# CNCdriver.net
KiCad netlist of a schematic drawn in EAGLE
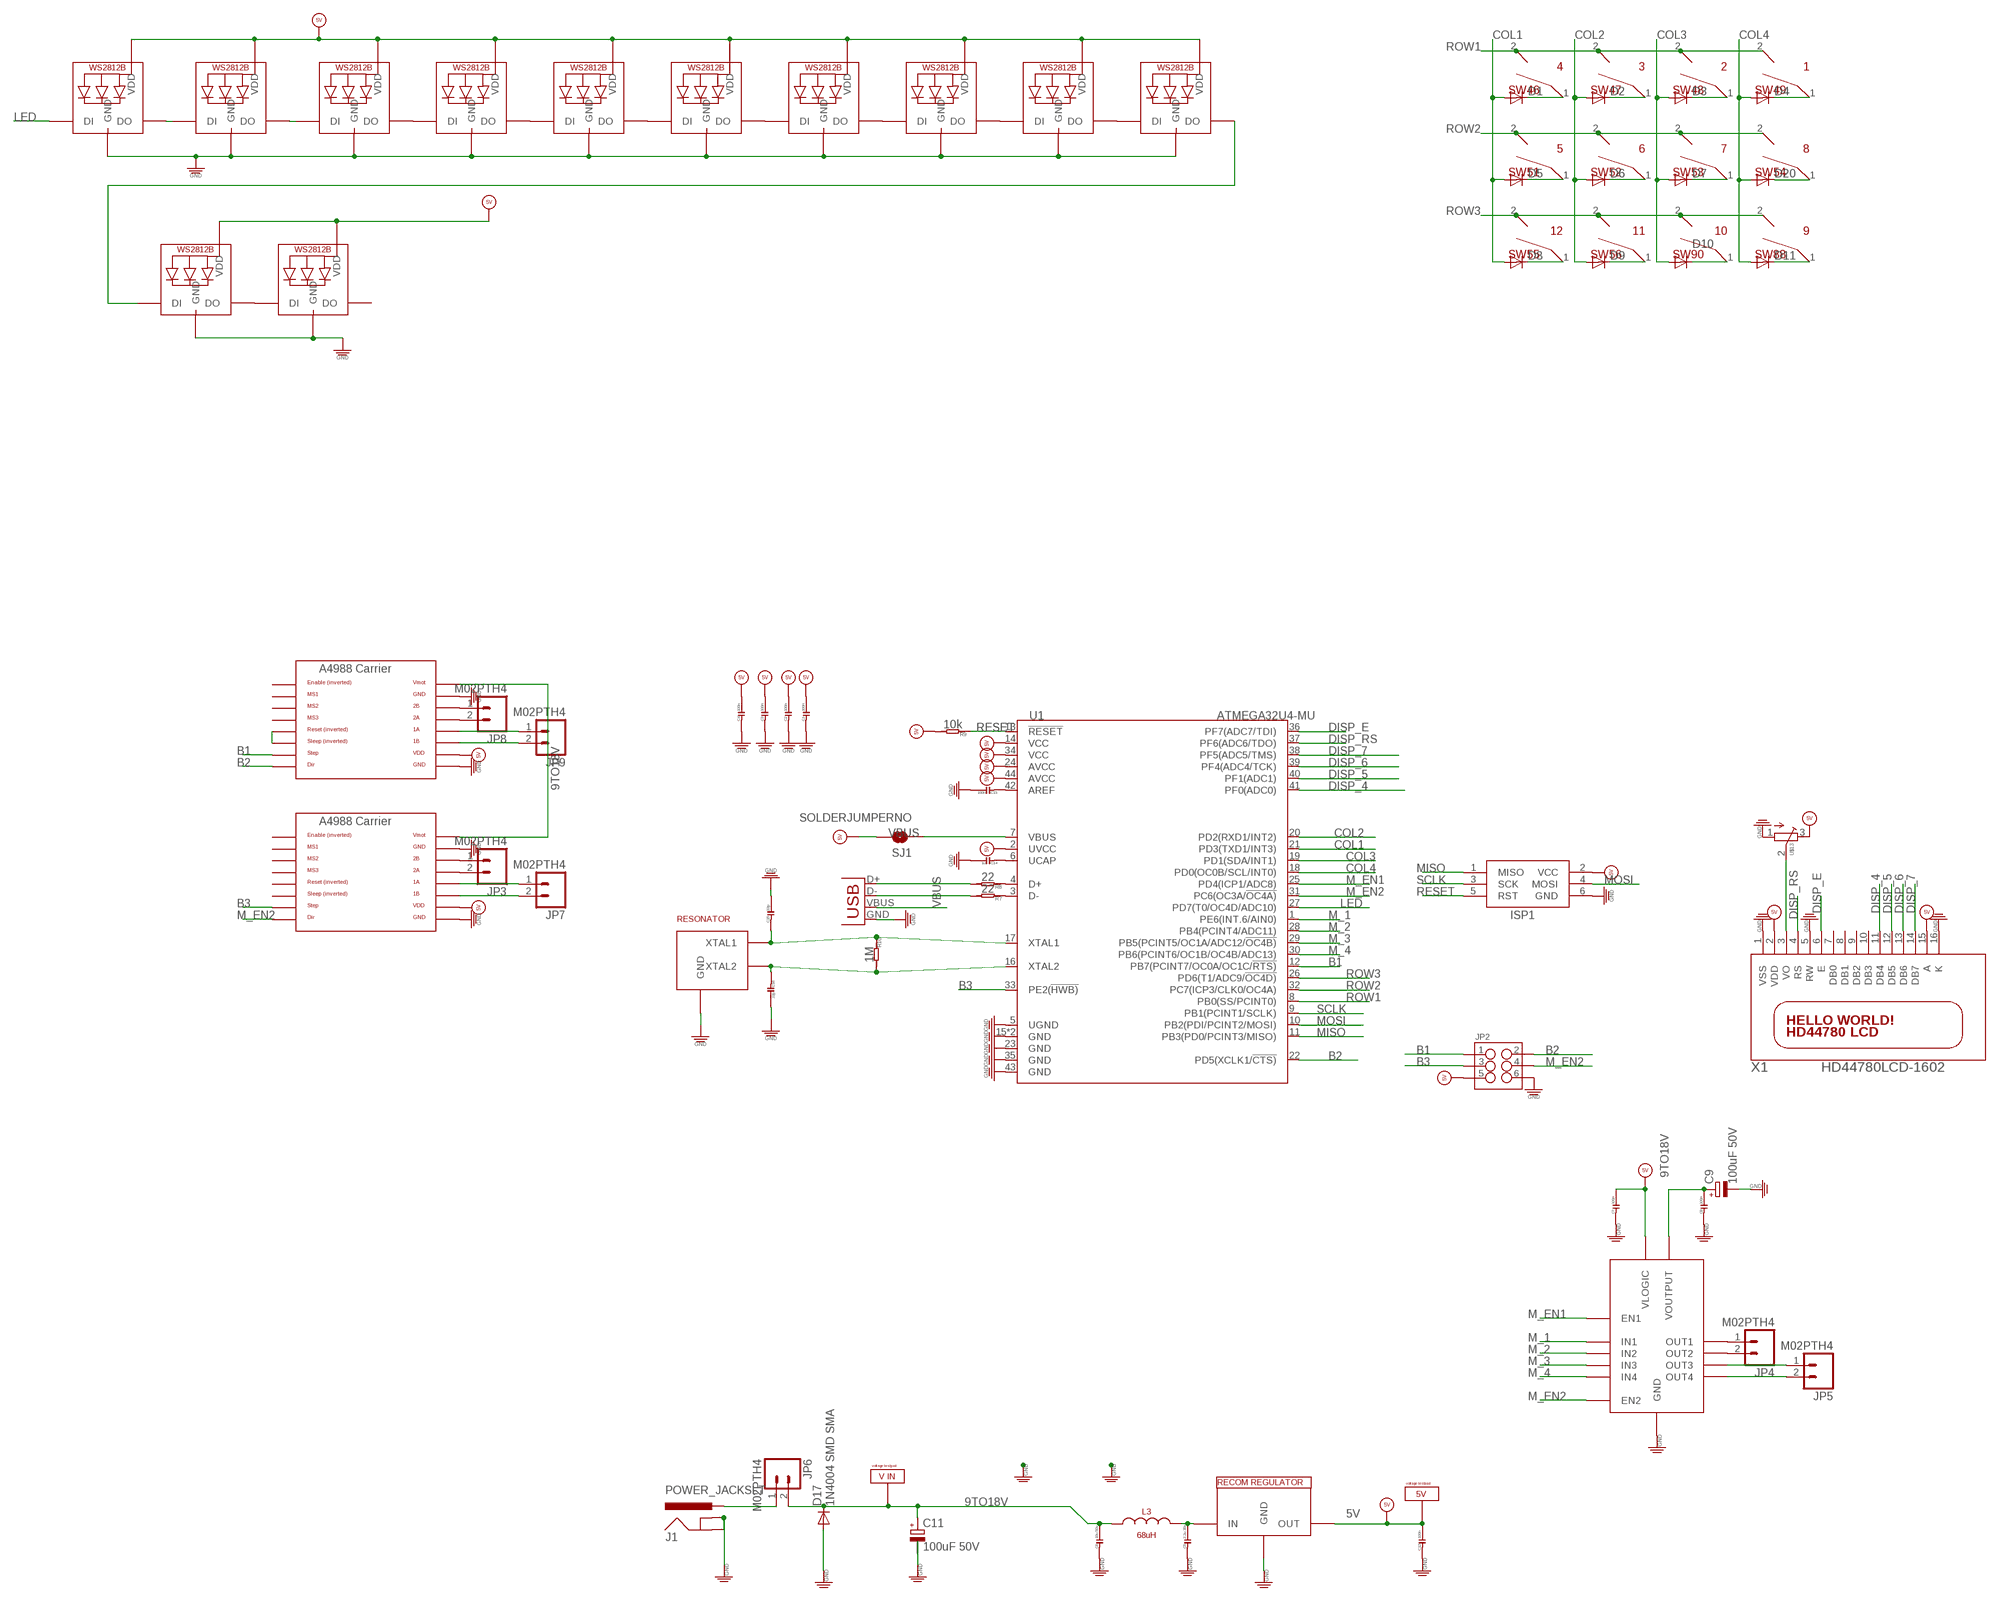
[diagram p0: schematic, sheet 1]

(export (version "E")
  (design (tool "Eeschema 10.0.6"))
  (components
    (comp (ref "C1")
      (value "100n")
      (footprint "eagle-import:C0603")
      (libsource (lib "eagle-import") (part "C-0603"))
    )
    (comp (ref "C2")
      (value "100n")
      (footprint "eagle-import:C0603")
      (libsource (lib "eagle-import") (part "C-0603"))
    )
    (comp (ref "C3")
      (value "100n")
      (footprint "eagle-import:C0603")
      (libsource (lib "eagle-import") (part "C-0603"))
    )
    (comp (ref "C4")
      (value "100n")
      (footprint "eagle-import:C0603")
      (libsource (lib "eagle-import") (part "C-0603"))
    )
    (comp (ref "C5")
      (value "2.2u 35v")
      (footprint "eagle-import:C0603")
      (libsource (lib "eagle-import") (part "C-0603"))
    )
    (comp (ref "C6")
      (value "10u 50v")
      (footprint "eagle-import:C0603")
      (libsource (lib "eagle-import") (part "C-0603"))
    )
    (comp (ref "C7")
      (value "100n")
      (footprint "eagle-import:C0603")
      (libsource (lib "eagle-import") (part "C-0603"))
    )
    (comp (ref "C8")
      (value "100n")
      (footprint "eagle-import:C0603")
      (libsource (lib "eagle-import") (part "C-0603"))
    )
    (comp (ref "C9")
      (value "100uF 50V")
      (footprint "eagle-import:153CLV-1010")
      (libsource (lib "eagle-import") (part "CPOL-EU153CLV-1010"))
    )
    (comp (ref "C11")
      (value "100uF 50V")
      (footprint "eagle-import:153CLV-1010")
      (libsource (lib "eagle-import") (part "CPOL-EU153CLV-1010"))
    )
    (comp (ref "C12")
      (value "100n")
      (footprint "eagle-import:C0603")
      (libsource (lib "eagle-import") (part "C-0603"))
    )
    (comp (ref "C13")
      (value "100n")
      (footprint "eagle-import:C0603")
      (libsource (lib "eagle-import") (part "C-0603"))
    )
    (comp (ref "C14")
      (value "1u")
      (footprint "eagle-import:C0603")
      (libsource (lib "eagle-import") (part "C-0603"))
    )
    (comp (ref "C15")
      (value "22p")
      (footprint "eagle-import:C0603")
      (libsource (lib "eagle-import") (part "C-0603"))
    )
    (comp (ref "C16")
      (value "22p")
      (footprint "eagle-import:C0603")
      (libsource (lib "eagle-import") (part "C-0603"))
    )
    (comp (ref "D1")
      (value "CGRM4001-G")
      (footprint "eagle-import:SOD-123_MINI-SMA")
      (libsource (lib "eagle-import") (part "CGRM400-G1"))
    )
    (comp (ref "D2")
      (value "CGRM4001-G")
      (footprint "eagle-import:SOD-123_MINI-SMA")
      (libsource (lib "eagle-import") (part "CGRM400-G1"))
    )
    (comp (ref "D3")
      (value "CGRM4001-G")
      (footprint "eagle-import:SOD-123_MINI-SMA")
      (libsource (lib "eagle-import") (part "CGRM400-G1"))
    )
    (comp (ref "D4")
      (value "CGRM4001-G")
      (footprint "eagle-import:SOD-123_MINI-SMA")
      (libsource (lib "eagle-import") (part "CGRM400-G1"))
    )
    (comp (ref "D5")
      (value "CGRM4001-G")
      (footprint "eagle-import:SOD-123_MINI-SMA")
      (libsource (lib "eagle-import") (part "CGRM400-G1"))
    )
    (comp (ref "D6")
      (value "CGRM4001-G")
      (footprint "eagle-import:SOD-123_MINI-SMA")
      (libsource (lib "eagle-import") (part "CGRM400-G1"))
    )
    (comp (ref "D7")
      (value "CGRM4001-G")
      (footprint "eagle-import:SOD-123_MINI-SMA")
      (libsource (lib "eagle-import") (part "CGRM400-G1"))
    )
    (comp (ref "D8")
      (value "CGRM4001-G")
      (footprint "eagle-import:SOD-123_MINI-SMA")
      (libsource (lib "eagle-import") (part "CGRM400-G1"))
    )
    (comp (ref "D9")
      (value "CGRM4001-G")
      (footprint "eagle-import:SOD-123_MINI-SMA")
      (libsource (lib "eagle-import") (part "CGRM400-G1"))
    )
    (comp (ref "D10")
      (value "CGRM4001-G")
      (footprint "eagle-import:SOD-123_MINI-SMA")
      (libsource (lib "eagle-import") (part "CGRM400-G1"))
    )
    (comp (ref "D11")
      (value "CGRM4001-G")
      (footprint "eagle-import:SOD-123_MINI-SMA")
      (libsource (lib "eagle-import") (part "CGRM400-G1"))
    )
    (comp (ref "D17")
      (value "1N4004 SMD SMA")
      (footprint "eagle-import:DO214AC")
      (libsource (lib "eagle-import") (part "DIODE-DO214AC"))
    )
    (comp (ref "D20")
      (value "CGRM4001-G")
      (footprint "eagle-import:SOD-123_MINI-SMA")
      (libsource (lib "eagle-import") (part "CGRM400-G1"))
    )
    (comp (ref "ISP1")
      (value "AVRISP-6")
      (footprint "eagle-import:AVRISP")
      (libsource (lib "eagle-import") (part "AVRISP-6"))
    )
    (comp (ref "J1")
      (value "POWER_JACKSLT")
      (footprint "eagle-import:POWER_JACK_SLOT")
      (libsource (lib "eagle-import") (part "POWER_JACKSLT"))
    )
    (comp (ref "JP1")
      (value "USB-B")
      (footprint "eagle-import:USB-B-PTH")
      (libsource (lib "eagle-import") (part "USBPTH"))
    )
    (comp (ref "JP2")
      (value "M03X2")
      (footprint "eagle-import:2X3-SHROUDED")
      (libsource (lib "eagle-import") (part "M03X2"))
    )
    (comp (ref "JP3")
      (value "M02PTH4")
      (footprint "eagle-import:1X02_XTRA_BIG")
      (libsource (lib "eagle-import") (part "M02PTH4"))
    )
    (comp (ref "JP4")
      (value "M02PTH4")
      (footprint "eagle-import:1X02_XTRA_BIG")
      (libsource (lib "eagle-import") (part "M02PTH4"))
    )
    (comp (ref "JP5")
      (value "M02PTH4")
      (footprint "eagle-import:1X02_XTRA_BIG")
      (libsource (lib "eagle-import") (part "M02PTH4"))
    )
    (comp (ref "JP6")
      (value "M02PTH4")
      (footprint "eagle-import:1X02_XTRA_BIG")
      (libsource (lib "eagle-import") (part "M02PTH4"))
    )
    (comp (ref "JP7")
      (value "M02PTH4")
      (footprint "eagle-import:1X02_XTRA_BIG")
      (libsource (lib "eagle-import") (part "M02PTH4"))
    )
    (comp (ref "JP8")
      (value "M02PTH4")
      (footprint "eagle-import:1X02_XTRA_BIG")
      (libsource (lib "eagle-import") (part "M02PTH4"))
    )
    (comp (ref "JP9")
      (value "M02PTH4")
      (footprint "eagle-import:1X02_XTRA_BIG")
      (libsource (lib "eagle-import") (part "M02PTH4"))
    )
    (comp (ref "L3")
      (value "68uH")
      (footprint "eagle-import:SWRB120XS")
      (libsource (lib "eagle-import") (part "L-SWRB1204S"))
    )
    (comp (ref "LED13")
      (value "WS2812B3535")
      (footprint "eagle-import:LED3535")
      (libsource (lib "eagle-import") (part "WS2812B3535"))
    )
    (comp (ref "LED14")
      (value "WS2812B3535")
      (footprint "eagle-import:LED3535")
      (libsource (lib "eagle-import") (part "WS2812B3535"))
    )
    (comp (ref "LED15")
      (value "WS2812B3535")
      (footprint "eagle-import:LED3535")
      (libsource (lib "eagle-import") (part "WS2812B3535"))
    )
    (comp (ref "LED16")
      (value "WS2812B3535")
      (footprint "eagle-import:LED3535")
      (libsource (lib "eagle-import") (part "WS2812B3535"))
    )
    (comp (ref "LED17")
      (value "WS2812B3535")
      (footprint "eagle-import:LED3535")
      (libsource (lib "eagle-import") (part "WS2812B3535"))
    )
    (comp (ref "LED18")
      (value "WS2812B3535")
      (footprint "eagle-import:LED3535")
      (libsource (lib "eagle-import") (part "WS2812B3535"))
    )
    (comp (ref "LED19")
      (value "WS2812B3535")
      (footprint "eagle-import:LED3535")
      (libsource (lib "eagle-import") (part "WS2812B3535"))
    )
    (comp (ref "LED20")
      (value "WS2812B3535")
      (footprint "eagle-import:LED3535")
      (libsource (lib "eagle-import") (part "WS2812B3535"))
    )
    (comp (ref "LED21")
      (value "WS2812B3535")
      (footprint "eagle-import:LED3535")
      (libsource (lib "eagle-import") (part "WS2812B3535"))
    )
    (comp (ref "LED22")
      (value "WS2812B3535")
      (footprint "eagle-import:LED3535")
      (libsource (lib "eagle-import") (part "WS2812B3535"))
    )
    (comp (ref "LED23")
      (value "WS2812B3535")
      (footprint "eagle-import:LED3535")
      (libsource (lib "eagle-import") (part "WS2812B3535"))
    )
    (comp (ref "LED24")
      (value "WS2812B3535")
      (footprint "eagle-import:LED3535")
      (libsource (lib "eagle-import") (part "WS2812B3535"))
    )
    (comp (ref "R7")
      (value "22")
      (footprint "eagle-import:R0603")
      (libsource (lib "eagle-import") (part "R-0603"))
    )
    (comp (ref "R8")
      (value "22")
      (footprint "eagle-import:R0603")
      (libsource (lib "eagle-import") (part "R-0603"))
    )
    (comp (ref "R9")
      (value "10k")
      (footprint "eagle-import:R0603")
      (libsource (lib "eagle-import") (part "R-0603"))
    )
    (comp (ref "R10")
      (value "1M")
      (footprint "eagle-import:R0603")
      (libsource (lib "eagle-import") (part "R-0603"))
    )
    (comp (ref "SJ1")
      (value "SOLDERJUMPERNO")
      (footprint "eagle-import:SJ_2S-NO")
      (libsource (lib "eagle-import") (part "SOLDERJUMPERNO"))
    )
    (comp (ref "SW46")
      (value "4")
      (footprint "eagle-import:MX1A-XXNW")
      (libsource (lib "eagle-import") (part "CHERRY_MX_WITH_FIXING_PINS"))
    )
    (comp (ref "SW47")
      (value "3")
      (footprint "eagle-import:MX1A-XXNW")
      (libsource (lib "eagle-import") (part "CHERRY_MX_WITH_FIXING_PINS"))
    )
    (comp (ref "SW48")
      (value "2")
      (footprint "eagle-import:MX1A-XXNW")
      (libsource (lib "eagle-import") (part "CHERRY_MX_WITH_FIXING_PINS"))
    )
    (comp (ref "SW49")
      (value "1")
      (footprint "eagle-import:MX1A-XXNW")
      (libsource (lib "eagle-import") (part "CHERRY_MX_WITH_FIXING_PINS"))
    )
    (comp (ref "SW51")
      (value "5")
      (footprint "eagle-import:MX1A-XXNW")
      (libsource (lib "eagle-import") (part "CHERRY_MX_WITH_FIXING_PINS"))
    )
    (comp (ref "SW52")
      (value "6")
      (footprint "eagle-import:MX1A-XXNW")
      (libsource (lib "eagle-import") (part "CHERRY_MX_WITH_FIXING_PINS"))
    )
    (comp (ref "SW53")
      (value "7")
      (footprint "eagle-import:MX1A-XXNW")
      (libsource (lib "eagle-import") (part "CHERRY_MX_WITH_FIXING_PINS"))
    )
    (comp (ref "SW54")
      (value "8")
      (footprint "eagle-import:MX1A-XXNW")
      (libsource (lib "eagle-import") (part "CHERRY_MX_WITH_FIXING_PINS"))
    )
    (comp (ref "SW55")
      (value "12")
      (footprint "eagle-import:MX1A-XXNW")
      (libsource (lib "eagle-import") (part "CHERRY_MX_WITH_FIXING_PINS"))
    )
    (comp (ref "SW56")
      (value "11")
      (footprint "eagle-import:MX1A-XXNW")
      (libsource (lib "eagle-import") (part "CHERRY_MX_WITH_FIXING_PINS"))
    )
    (comp (ref "SW88")
      (value "9")
      (footprint "eagle-import:MX1A-XXNW")
      (libsource (lib "eagle-import") (part "CHERRY_MX_WITH_FIXING_PINS"))
    )
    (comp (ref "SW90")
      (value "10")
      (footprint "eagle-import:MX1A-XXNW")
      (libsource (lib "eagle-import") (part "CHERRY_MX_WITH_FIXING_PINS"))
    )
    (comp (ref "U$9")
      (value "L293D")
      (footprint "eagle-import:SO20")
      (libsource (lib "eagle-import") (part "L293D"))
    )
    (comp (ref "U$13")
      (value "TRIMPOTTC33X")
      (footprint "eagle-import:TC33X")
      (libsource (lib "eagle-import") (part "TRIMPOTTC33X"))
    )
    (comp (ref "U$15")
      (value "A4983CARRIER")
      (footprint "eagle-import:A4988BREAKOUT")
      (libsource (lib "eagle-import") (part "A4983CARRIER"))
    )
    (comp (ref "U$16")
      (value "A4983CARRIER")
      (footprint "eagle-import:A4988BREAKOUT")
      (libsource (lib "eagle-import") (part "A4983CARRIER"))
    )
    (comp (ref "U$17")
      (value "RECOM_REGULATOR")
      (footprint "eagle-import:R-78E5.0-1.0")
      (libsource (lib "eagle-import") (part "RECOM_REGULATOR"))
    )
    (comp (ref "U$25")
      (value "VOLTAGETESTPAD")
      (footprint "eagle-import:POWERTESTPAD")
      (fields (field (name "DESC") "5V"))
      (libsource (lib "eagle-import") (part "VOLTAGETESTPAD"))
    )
    (comp (ref "U$29")
      (value "VOLTAGETESTPAD")
      (footprint "eagle-import:POWERTESTPAD")
      (fields (field (name "DESC") "V IN"))
      (libsource (lib "eagle-import") (part "VOLTAGETESTPAD"))
    )
    (comp (ref "U$60")
      (value "RESONATOR")
      (footprint "eagle-import:16MHZXTAL")
      (libsource (lib "eagle-import") (part "RESONATOR"))
    )
    (comp (ref "U1")
      (value "ATMEGA32U4-MU")
      (footprint "eagle-import:QFN44")
      (libsource (lib "eagle-import") (part "ATMEGA32U4-MU"))
    )
    (comp (ref "X1")
      (value "HD44780LCD-1602")
      (footprint "eagle-import:LCD1602")
      (libsource (lib "eagle-import") (part "HD44780LCD-1602"))
    )
  )
  (nets
    (net (code "1") (name "/9TO18V") (class "Default")
      (node (ref "C11") (pin "+") (pinfunction "+_+") (pintype "passive"))
      (node (ref "C6") (pin "2") (pinfunction "2_2") (pintype "bidirectional"))
      (node (ref "C8") (pin "2") (pinfunction "2_2") (pintype "bidirectional"))
      (node (ref "C9") (pin "+") (pinfunction "+_+") (pintype "passive"))
      (node (ref "D17") (pin "C") (pinfunction "C_C") (pintype "passive"))
      (node (ref "JP6") (pin "2") (pinfunction "2_2") (pintype "passive"))
      (node (ref "L3") (pin "P$1") (pinfunction "P$1_P$1") (pintype "bidirectional"))
      (node (ref "U$15") (pin "VMOT") (pinfunction "VMOT_VMOT") (pintype "power_in"))
      (node (ref "U$16") (pin "VMOT") (pinfunction "VMOT_VMOT") (pintype "power_in"))
      (node (ref "U$29") (pin "P$1") (pinfunction "VOLTAGE_P$1") (pintype "bidirectional"))
      (node (ref "U$29") (pin "P$2") (pinfunction "VOLTAGE_P$2") (pintype "bidirectional"))
      (node (ref "U$29") (pin "P$3") (pinfunction "VOLTAGE_P$3") (pintype "bidirectional"))
      (node (ref "U$9") (pin "P$10") (pinfunction "VOUTPUT_P$10") (pintype "bidirectional"))
    )
    (net (code "2") (name "/B1") (class "Default")
      (node (ref "JP2") (pin "1") (pinfunction "1_1") (pintype "bidirectional"))
      (node (ref "U$15") (pin "STEP") (pinfunction "STEP_STEP") (pintype "input"))
      (node (ref "U1") (pin "12") (pinfunction "PB7(PCINT7/OC0A/OC1C/~{RTS})_12") (pintype "bidirectional"))
    )
    (net (code "3") (name "/B2") (class "Default")
      (node (ref "JP2") (pin "2") (pinfunction "2_2") (pintype "bidirectional"))
      (node (ref "U$15") (pin "DIR") (pinfunction "DIR_DIR") (pintype "input"))
      (node (ref "U1") (pin "22") (pinfunction "PD5(XCLK1/~{CTS})_22") (pintype "bidirectional"))
    )
    (net (code "4") (name "/B3") (class "Default")
      (node (ref "JP2") (pin "3") (pinfunction "3_3") (pintype "bidirectional"))
      (node (ref "U$16") (pin "STEP") (pinfunction "STEP_STEP") (pintype "input"))
      (node (ref "U1") (pin "33") (pinfunction "PE2(~{HWB})_33") (pintype "bidirectional"))
    )
    (net (code "5") (name "/COL1") (class "Default")
      (node (ref "D1") (pin "A") (pinfunction "A_A") (pintype "passive"))
      (node (ref "D5") (pin "A") (pinfunction "A_A") (pintype "passive"))
      (node (ref "D8") (pin "A") (pinfunction "A_A") (pintype "passive"))
      (node (ref "U1") (pin "21") (pinfunction "PD3(TXD1/INT3)_21") (pintype "bidirectional"))
    )
    (net (code "6") (name "/COL2") (class "Default")
      (node (ref "D2") (pin "A") (pinfunction "A_A") (pintype "passive"))
      (node (ref "D6") (pin "A") (pinfunction "A_A") (pintype "passive"))
      (node (ref "D9") (pin "A") (pinfunction "A_A") (pintype "passive"))
      (node (ref "U1") (pin "20") (pinfunction "PD2(RXD1/INT2)_20") (pintype "bidirectional"))
    )
    (net (code "7") (name "/COL3") (class "Default")
      (node (ref "D10") (pin "A") (pinfunction "A_A") (pintype "passive"))
      (node (ref "D3") (pin "A") (pinfunction "A_A") (pintype "passive"))
      (node (ref "D7") (pin "A") (pinfunction "A_A") (pintype "passive"))
      (node (ref "U1") (pin "19") (pinfunction "PD1(SDA/INT1)_19") (pintype "bidirectional"))
    )
    (net (code "8") (name "/COL4") (class "Default")
      (node (ref "D11") (pin "A") (pinfunction "A_A") (pintype "passive"))
      (node (ref "D20") (pin "A") (pinfunction "A_A") (pintype "passive"))
      (node (ref "D4") (pin "A") (pinfunction "A_A") (pintype "passive"))
      (node (ref "U1") (pin "18") (pinfunction "PD0(OC0B/SCL/INT0)_18") (pintype "bidirectional"))
    )
    (net (code "9") (name "/DISP_4") (class "Default")
      (node (ref "U1") (pin "41") (pinfunction "PF0(ADC0)_41") (pintype "bidirectional"))
      (node (ref "X1") (pin "11") (pinfunction "DB4_11") (pintype "bidirectional"))
    )
    (net (code "10") (name "/DISP_5") (class "Default")
      (node (ref "U1") (pin "40") (pinfunction "PF1(ADC1)_40") (pintype "bidirectional"))
      (node (ref "X1") (pin "12") (pinfunction "DB5_12") (pintype "bidirectional"))
    )
    (net (code "11") (name "/DISP_6") (class "Default")
      (node (ref "U1") (pin "39") (pinfunction "PF4(ADC4/TCK)_39") (pintype "bidirectional"))
      (node (ref "X1") (pin "13") (pinfunction "DB6_13") (pintype "bidirectional"))
    )
    (net (code "12") (name "/DISP_7") (class "Default")
      (node (ref "U1") (pin "38") (pinfunction "PF5(ADC5/TMS)_38") (pintype "bidirectional"))
      (node (ref "X1") (pin "14") (pinfunction "DB7_14") (pintype "bidirectional"))
    )
    (net (code "13") (name "/DISP_E") (class "Default")
      (node (ref "U1") (pin "36") (pinfunction "PF7(ADC7/TDI)_36") (pintype "bidirectional"))
      (node (ref "X1") (pin "6") (pinfunction "E_6") (pintype "input"))
    )
    (net (code "14") (name "/DISP_RS") (class "Default")
      (node (ref "U1") (pin "37") (pinfunction "PF6(ADC6/TDO)_37") (pintype "bidirectional"))
      (node (ref "X1") (pin "4") (pinfunction "RS_4") (pintype "input"))
    )
    (net (code "15") (name "/LED") (class "Default")
      (node (ref "LED13") (pin "4") (pinfunction "DI_4") (pintype "input"))
      (node (ref "U1") (pin "27") (pinfunction "PD7(T0/OC4D/ADC10)_27") (pintype "bidirectional"))
    )
    (net (code "16") (name "/MISO") (class "Default")
      (node (ref "ISP1") (pin "1") (pinfunction "MISO_1") (pintype "input"))
      (node (ref "U1") (pin "11") (pinfunction "PB3(PD0/PCINT3/MISO)_11") (pintype "bidirectional"))
    )
    (net (code "17") (name "/MOSI") (class "Default")
      (node (ref "ISP1") (pin "4") (pinfunction "MOSI_4") (pintype "output"))
      (node (ref "U1") (pin "10") (pinfunction "PB2(PDI/PCINT2/MOSI)_10") (pintype "bidirectional"))
    )
    (net (code "18") (name "/M_1") (class "Default")
      (node (ref "U$9") (pin "P$2") (pinfunction "IN1_P$2") (pintype "bidirectional"))
      (node (ref "U1") (pin "1") (pinfunction "PE6(INT.6/AIN0)_1") (pintype "bidirectional"))
    )
    (net (code "19") (name "/M_2") (class "Default")
      (node (ref "U$9") (pin "P$9") (pinfunction "IN2_P$9") (pintype "bidirectional"))
      (node (ref "U1") (pin "28") (pinfunction "PB4(PCINT4/ADC11)_28") (pintype "bidirectional"))
    )
    (net (code "20") (name "/M_3") (class "Default")
      (node (ref "U$9") (pin "P$12") (pinfunction "IN3_P$12") (pintype "bidirectional"))
      (node (ref "U1") (pin "29") (pinfunction "PB5(PCINT5/OC1A/ADC12/~{OC4B})_29") (pintype "bidirectional"))
    )
    (net (code "21") (name "/M_4") (class "Default")
      (node (ref "U$9") (pin "P$19") (pinfunction "IN4_P$19") (pintype "bidirectional"))
      (node (ref "U1") (pin "30") (pinfunction "PB6(PCINT6/OC1B/OC4B/ADC13)_30") (pintype "bidirectional"))
    )
    (net (code "22") (name "/M_EN1") (class "Default")
      (node (ref "U$9") (pin "P$1") (pinfunction "EN1_P$1") (pintype "bidirectional"))
      (node (ref "U1") (pin "25") (pinfunction "PD4(ICP1/ADC8)_25") (pintype "bidirectional"))
    )
    (net (code "23") (name "/M_EN2") (class "Default")
      (node (ref "JP2") (pin "4") (pinfunction "4_4") (pintype "bidirectional"))
      (node (ref "U$16") (pin "DIR") (pinfunction "DIR_DIR") (pintype "input"))
      (node (ref "U$9") (pin "P$11") (pinfunction "EN2_P$11") (pintype "bidirectional"))
      (node (ref "U1") (pin "31") (pinfunction "PC6(OC3A/~{OC4A})_31") (pintype "bidirectional"))
    )
    (net (code "24") (name "/RESET") (class "Default")
      (node (ref "ISP1") (pin "5") (pinfunction "RST_5") (pintype "output"))
      (node (ref "R9") (pin "1") (pinfunction "1_1") (pintype "bidirectional"))
      (node (ref "U1") (pin "13") (pinfunction "~{RESET}_13") (pintype "bidirectional"))
    )
    (net (code "25") (name "/ROW1") (class "Default")
      (node (ref "SW46") (pin "2") (pinfunction "2_2") (pintype "passive"))
      (node (ref "SW47") (pin "2") (pinfunction "2_2") (pintype "passive"))
      (node (ref "SW48") (pin "2") (pinfunction "2_2") (pintype "passive"))
      (node (ref "SW49") (pin "2") (pinfunction "2_2") (pintype "passive"))
      (node (ref "U1") (pin "8") (pinfunction "PB0(SS/PCINT0)_8") (pintype "bidirectional"))
    )
    (net (code "26") (name "/ROW2") (class "Default")
      (node (ref "SW51") (pin "2") (pinfunction "2_2") (pintype "passive"))
      (node (ref "SW52") (pin "2") (pinfunction "2_2") (pintype "passive"))
      (node (ref "SW53") (pin "2") (pinfunction "2_2") (pintype "passive"))
      (node (ref "SW54") (pin "2") (pinfunction "2_2") (pintype "passive"))
      (node (ref "U1") (pin "32") (pinfunction "PC7(ICP3/CLK0/OC4A)_32") (pintype "bidirectional"))
    )
    (net (code "27") (name "/ROW3") (class "Default")
      (node (ref "SW55") (pin "2") (pinfunction "2_2") (pintype "passive"))
      (node (ref "SW56") (pin "2") (pinfunction "2_2") (pintype "passive"))
      (node (ref "SW88") (pin "2") (pinfunction "2_2") (pintype "passive"))
      (node (ref "SW90") (pin "2") (pinfunction "2_2") (pintype "passive"))
      (node (ref "U1") (pin "26") (pinfunction "PD6(T1/ADC9/~{OC4D})_26") (pintype "bidirectional"))
    )
    (net (code "28") (name "/SCLK") (class "Default")
      (node (ref "ISP1") (pin "3") (pinfunction "SCK_3") (pintype "output"))
      (node (ref "U1") (pin "9") (pinfunction "PB1(PCINT1/SCLK)_9") (pintype "bidirectional"))
    )
    (net (code "29") (name "/VBUS") (class "Default")
      (node (ref "JP1") (pin "VBUS") (pinfunction "VBUS_VBUS") (pintype "bidirectional"))
      (node (ref "SJ1") (pin "1") (pinfunction "1_1") (pintype "passive"))
      (node (ref "U1") (pin "7") (pinfunction "VBUS_7") (pintype "bidirectional"))
    )
    (net (code "30") (name "5V") (class "Default")
      (node (ref "C1") (pin "2") (pinfunction "2_2") (pintype "bidirectional"))
      (node (ref "C12") (pin "2") (pinfunction "2_2") (pintype "bidirectional"))
      (node (ref "C2") (pin "2") (pinfunction "2_2") (pintype "bidirectional"))
      (node (ref "C3") (pin "2") (pinfunction "2_2") (pintype "bidirectional"))
      (node (ref "C4") (pin "2") (pinfunction "2_2") (pintype "bidirectional"))
      (node (ref "C7") (pin "2") (pinfunction "2_2") (pintype "bidirectional"))
      (node (ref "ISP1") (pin "2") (pinfunction "VCC_2") (pintype "power_in"))
      (node (ref "JP2") (pin "5") (pinfunction "5_5") (pintype "bidirectional"))
      (node (ref "LED13") (pin "1") (pinfunction "VDD_1") (pintype "power_in"))
      (node (ref "LED14") (pin "1") (pinfunction "VDD_1") (pintype "power_in"))
      (node (ref "LED15") (pin "1") (pinfunction "VDD_1") (pintype "power_in"))
      (node (ref "LED16") (pin "1") (pinfunction "VDD_1") (pintype "power_in"))
      (node (ref "LED17") (pin "1") (pinfunction "VDD_1") (pintype "power_in"))
      (node (ref "LED18") (pin "1") (pinfunction "VDD_1") (pintype "power_in"))
      (node (ref "LED19") (pin "1") (pinfunction "VDD_1") (pintype "power_in"))
      (node (ref "LED20") (pin "1") (pinfunction "VDD_1") (pintype "power_in"))
      (node (ref "LED21") (pin "1") (pinfunction "VDD_1") (pintype "power_in"))
      (node (ref "LED22") (pin "1") (pinfunction "VDD_1") (pintype "power_in"))
      (node (ref "LED23") (pin "1") (pinfunction "VDD_1") (pintype "power_in"))
      (node (ref "LED24") (pin "1") (pinfunction "VDD_1") (pintype "power_in"))
      (node (ref "R9") (pin "2") (pinfunction "2_2") (pintype "bidirectional"))
      (node (ref "SJ1") (pin "2") (pinfunction "2_2") (pintype "passive"))
      (node (ref "U$13") (pin "3") (pinfunction "E_3") (pintype "passive"))
      (node (ref "U$15") (pin "VDD") (pinfunction "VDD_VDD") (pintype "power_in"))
      (node (ref "U$16") (pin "VDD") (pinfunction "VDD_VDD") (pintype "power_in"))
      (node (ref "U$17") (pin "P$3") (pinfunction "OUT_P$3") (pintype "bidirectional"))
      (node (ref "U$25") (pin "P$1") (pinfunction "VOLTAGE_P$1") (pintype "bidirectional"))
      (node (ref "U$25") (pin "P$2") (pinfunction "VOLTAGE_P$2") (pintype "bidirectional"))
      (node (ref "U$25") (pin "P$3") (pinfunction "VOLTAGE_P$3") (pintype "bidirectional"))
      (node (ref "U$9") (pin "P$20") (pinfunction "VLOGIC_P$20") (pintype "bidirectional"))
      (node (ref "U1") (pin "14") (pinfunction "VCC_14") (pintype "bidirectional"))
      (node (ref "U1") (pin "2") (pinfunction "UVCC_2") (pintype "bidirectional"))
      (node (ref "U1") (pin "24") (pinfunction "AVCC_24") (pintype "bidirectional"))
      (node (ref "U1") (pin "34") (pinfunction "VCC_34") (pintype "bidirectional"))
      (node (ref "U1") (pin "44") (pinfunction "AVCC_44") (pintype "bidirectional"))
      (node (ref "X1") (pin "15") (pinfunction "A_15") (pintype "input"))
      (node (ref "X1") (pin "2") (pinfunction "VDD_2") (pintype "power_in"))
    )
    (net (code "31") (name "GND") (class "Default")
      (node (ref "C1") (pin "1") (pinfunction "1_1") (pintype "bidirectional"))
      (node (ref "C11") (pin "-") (pinfunction "-_-") (pintype "passive"))
      (node (ref "C12") (pin "1") (pinfunction "1_1") (pintype "bidirectional"))
      (node (ref "C13") (pin "2") (pinfunction "2_2") (pintype "bidirectional"))
      (node (ref "C14") (pin "2") (pinfunction "2_2") (pintype "bidirectional"))
      (node (ref "C15") (pin "2") (pinfunction "2_2") (pintype "bidirectional"))
      (node (ref "C16") (pin "2") (pinfunction "2_2") (pintype "bidirectional"))
      (node (ref "C2") (pin "1") (pinfunction "1_1") (pintype "bidirectional"))
      (node (ref "C3") (pin "1") (pinfunction "1_1") (pintype "bidirectional"))
      (node (ref "C4") (pin "1") (pinfunction "1_1") (pintype "bidirectional"))
      (node (ref "C5") (pin "1") (pinfunction "1_1") (pintype "bidirectional"))
      (node (ref "C6") (pin "1") (pinfunction "1_1") (pintype "bidirectional"))
      (node (ref "C7") (pin "1") (pinfunction "1_1") (pintype "bidirectional"))
      (node (ref "C8") (pin "1") (pinfunction "1_1") (pintype "bidirectional"))
      (node (ref "C9") (pin "-") (pinfunction "-_-") (pintype "passive"))
      (node (ref "D17") (pin "A") (pinfunction "A_A") (pintype "passive"))
      (node (ref "ISP1") (pin "6") (pinfunction "GND_6") (pintype "power_in"))
      (node (ref "J1") (pin "GND@1") (pinfunction "GNDBREAK_GND@1") (pintype "bidirectional"))
      (node (ref "J1") (pin "GND@2") (pinfunction "GND_GND@2") (pintype "bidirectional"))
      (node (ref "JP1") (pin "GND") (pinfunction "GND_GND") (pintype "bidirectional"))
      (node (ref "JP2") (pin "6") (pinfunction "6_6") (pintype "bidirectional"))
      (node (ref "LED13") (pin "3") (pinfunction "GND_3") (pintype "power_in"))
      (node (ref "LED14") (pin "3") (pinfunction "GND_3") (pintype "power_in"))
      (node (ref "LED15") (pin "3") (pinfunction "GND_3") (pintype "power_in"))
      (node (ref "LED16") (pin "3") (pinfunction "GND_3") (pintype "power_in"))
      (node (ref "LED17") (pin "3") (pinfunction "GND_3") (pintype "power_in"))
      (node (ref "LED18") (pin "3") (pinfunction "GND_3") (pintype "power_in"))
      (node (ref "LED19") (pin "3") (pinfunction "GND_3") (pintype "power_in"))
      (node (ref "LED20") (pin "3") (pinfunction "GND_3") (pintype "power_in"))
      (node (ref "LED21") (pin "3") (pinfunction "GND_3") (pintype "power_in"))
      (node (ref "LED22") (pin "3") (pinfunction "GND_3") (pintype "power_in"))
      (node (ref "LED23") (pin "3") (pinfunction "GND_3") (pintype "power_in"))
      (node (ref "LED24") (pin "3") (pinfunction "GND_3") (pintype "power_in"))
      (node (ref "U$13") (pin "1") (pinfunction "A_1") (pintype "passive"))
      (node (ref "U$15") (pin "GND") (pinfunction "GND_GND") (pintype "power_in"))
      (node (ref "U$15") (pin "GND@0") (pinfunction "GND_GND@0") (pintype "power_in"))
      (node (ref "U$16") (pin "GND") (pinfunction "GND_GND") (pintype "power_in"))
      (node (ref "U$16") (pin "GND@0") (pinfunction "GND_GND@0") (pintype "power_in"))
      (node (ref "U$17") (pin "P$2") (pinfunction "GND_P$2") (pintype "bidirectional"))
      (node (ref "U$60") (pin "P$2") (pinfunction "GND_P$2") (pintype "bidirectional"))
      (node (ref "U$60") (pin "P$4") (pinfunction "GND_P$4") (pintype "bidirectional"))
      (node (ref "U$9") (pin "P$14") (pinfunction "GND_P$14") (pintype "bidirectional"))
      (node (ref "U$9") (pin "P$15") (pinfunction "GND_P$15") (pintype "bidirectional"))
      (node (ref "U$9") (pin "P$16") (pinfunction "GND_P$16") (pintype "bidirectional"))
      (node (ref "U$9") (pin "P$17") (pinfunction "GND_P$17") (pintype "bidirectional"))
      (node (ref "U$9") (pin "P$4") (pinfunction "GND_P$4") (pintype "bidirectional"))
      (node (ref "U$9") (pin "P$5") (pinfunction "GND_P$5") (pintype "bidirectional"))
      (node (ref "U$9") (pin "P$6") (pinfunction "GND_P$6") (pintype "bidirectional"))
      (node (ref "U$9") (pin "P$7") (pinfunction "GND_P$7") (pintype "bidirectional"))
      (node (ref "U1") (pin "15") (pinfunction "GND_15") (pintype "bidirectional"))
      (node (ref "U1") (pin "23") (pinfunction "GND_23") (pintype "bidirectional"))
      (node (ref "U1") (pin "35") (pinfunction "GND_35") (pintype "bidirectional"))
      (node (ref "U1") (pin "43") (pinfunction "GND_43") (pintype "bidirectional"))
      (node (ref "U1") (pin "5") (pinfunction "UGND_5") (pintype "bidirectional"))
      (node (ref "U1") (pin "TAB") (pinfunction "GND_TAB") (pintype "bidirectional"))
      (node (ref "X1") (pin "1") (pinfunction "VSS_1") (pintype "power_in"))
      (node (ref "X1") (pin "16") (pinfunction "K_16") (pintype "input"))
      (node (ref "X1") (pin "5") (pinfunction "RW_5") (pintype "input"))
    )
    (net (code "32") (name "Net-(D1-PadC)") (class "Default")
      (node (ref "D1") (pin "C") (pinfunction "C_C") (pintype "passive"))
      (node (ref "SW46") (pin "1") (pinfunction "1_1") (pintype "passive"))
    )
    (net (code "33") (name "Net-(D2-PadC)") (class "Default")
      (node (ref "D2") (pin "C") (pinfunction "C_C") (pintype "passive"))
      (node (ref "SW47") (pin "1") (pinfunction "1_1") (pintype "passive"))
    )
    (net (code "34") (name "Net-(D3-PadC)") (class "Default")
      (node (ref "D3") (pin "C") (pinfunction "C_C") (pintype "passive"))
      (node (ref "SW48") (pin "1") (pinfunction "1_1") (pintype "passive"))
    )
    (net (code "35") (name "Net-(D4-PadC)") (class "Default")
      (node (ref "D4") (pin "C") (pinfunction "C_C") (pintype "passive"))
      (node (ref "SW49") (pin "1") (pinfunction "1_1") (pintype "passive"))
    )
    (net (code "36") (name "Net-(D5-PadC)") (class "Default")
      (node (ref "D5") (pin "C") (pinfunction "C_C") (pintype "passive"))
      (node (ref "SW51") (pin "1") (pinfunction "1_1") (pintype "passive"))
    )
    (net (code "37") (name "Net-(D6-PadC)") (class "Default")
      (node (ref "D6") (pin "C") (pinfunction "C_C") (pintype "passive"))
      (node (ref "SW52") (pin "1") (pinfunction "1_1") (pintype "passive"))
    )
    (net (code "38") (name "Net-(D7-PadC)") (class "Default")
      (node (ref "D7") (pin "C") (pinfunction "C_C") (pintype "passive"))
      (node (ref "SW53") (pin "1") (pinfunction "1_1") (pintype "passive"))
    )
    (net (code "39") (name "Net-(D8-PadC)") (class "Default")
      (node (ref "D8") (pin "C") (pinfunction "C_C") (pintype "passive"))
      (node (ref "SW55") (pin "1") (pinfunction "1_1") (pintype "passive"))
    )
    (net (code "40") (name "Net-(D9-PadC)") (class "Default")
      (node (ref "D9") (pin "C") (pinfunction "C_C") (pintype "passive"))
      (node (ref "SW56") (pin "1") (pinfunction "1_1") (pintype "passive"))
    )
    (net (code "41") (name "Net-(D10-PadC)") (class "Default")
      (node (ref "D10") (pin "C") (pinfunction "C_C") (pintype "passive"))
      (node (ref "SW90") (pin "1") (pinfunction "1_1") (pintype "passive"))
    )
    (net (code "42") (name "Net-(D11-PadC)") (class "Default")
      (node (ref "D11") (pin "C") (pinfunction "C_C") (pintype "passive"))
      (node (ref "SW88") (pin "1") (pinfunction "1_1") (pintype "passive"))
    )
    (net (code "43") (name "Net-(D20-PadC)") (class "Default")
      (node (ref "D20") (pin "C") (pinfunction "C_C") (pintype "passive"))
      (node (ref "SW54") (pin "1") (pinfunction "1_1") (pintype "passive"))
    )
    (net (code "44") (name "Net-(J1-PadPWR)") (class "Default")
      (node (ref "J1") (pin "PWR") (pinfunction "PWR_PWR") (pintype "bidirectional"))
      (node (ref "JP6") (pin "1") (pinfunction "1_1") (pintype "passive"))
    )
    (net (code "45") (name "Net-(JP1-PadD+)") (class "Default")
      (node (ref "JP1") (pin "D+") (pinfunction "D+_D+") (pintype "bidirectional"))
      (node (ref "R8") (pin "2") (pinfunction "2_2") (pintype "bidirectional"))
    )
    (net (code "46") (name "Net-(JP1-PadD-)") (class "Default")
      (node (ref "JP1") (pin "D-") (pinfunction "D-_D-") (pintype "bidirectional"))
      (node (ref "R7") (pin "2") (pinfunction "2_2") (pintype "bidirectional"))
    )
    (net (code "47") (name "Net-(JP3-Pad1)") (class "Default")
      (node (ref "JP3") (pin "1") (pinfunction "1_1") (pintype "passive"))
      (node (ref "U$16") (pin "2B") (pinfunction "2B_2B") (pintype "output"))
    )
    (net (code "48") (name "Net-(JP3-Pad2)") (class "Default")
      (node (ref "JP3") (pin "2") (pinfunction "2_2") (pintype "passive"))
      (node (ref "U$16") (pin "2A") (pinfunction "2A_2A") (pintype "output"))
    )
    (net (code "49") (name "Net-(JP7-Pad1)") (class "Default")
      (node (ref "JP7") (pin "1") (pinfunction "1_1") (pintype "passive"))
      (node (ref "U$16") (pin "1A") (pinfunction "1A_1A") (pintype "output"))
    )
    (net (code "50") (name "Net-(JP7-Pad2)") (class "Default")
      (node (ref "JP7") (pin "2") (pinfunction "2_2") (pintype "passive"))
      (node (ref "U$16") (pin "1B") (pinfunction "1B_1B") (pintype "output"))
    )
    (net (code "51") (name "Net-(JP8-Pad1)") (class "Default")
      (node (ref "JP8") (pin "1") (pinfunction "1_1") (pintype "passive"))
      (node (ref "U$15") (pin "2B") (pinfunction "2B_2B") (pintype "output"))
    )
    (net (code "52") (name "Net-(JP8-Pad2)") (class "Default")
      (node (ref "JP8") (pin "2") (pinfunction "2_2") (pintype "passive"))
      (node (ref "U$15") (pin "2A") (pinfunction "2A_2A") (pintype "output"))
    )
    (net (code "53") (name "Net-(JP9-Pad1)") (class "Default")
      (node (ref "JP9") (pin "1") (pinfunction "1_1") (pintype "passive"))
      (node (ref "U$15") (pin "1A") (pinfunction "1A_1A") (pintype "output"))
    )
    (net (code "54") (name "Net-(JP9-Pad2)") (class "Default")
      (node (ref "JP9") (pin "2") (pinfunction "2_2") (pintype "passive"))
      (node (ref "U$15") (pin "1B") (pinfunction "1B_1B") (pintype "output"))
    )
    (net (code "55") (name "Net-(LED13-DO)") (class "Default")
      (node (ref "LED13") (pin "2") (pinfunction "DO_2") (pintype "output"))
      (node (ref "LED14") (pin "4") (pinfunction "DI_4") (pintype "input"))
    )
    (net (code "56") (name "Net-(LED14-DO)") (class "Default")
      (node (ref "LED14") (pin "2") (pinfunction "DO_2") (pintype "output"))
      (node (ref "LED15") (pin "4") (pinfunction "DI_4") (pintype "input"))
    )
    (net (code "57") (name "Net-(LED15-DO)") (class "Default")
      (node (ref "LED15") (pin "2") (pinfunction "DO_2") (pintype "output"))
      (node (ref "LED16") (pin "4") (pinfunction "DI_4") (pintype "input"))
    )
    (net (code "58") (name "Net-(LED16-DO)") (class "Default")
      (node (ref "LED16") (pin "2") (pinfunction "DO_2") (pintype "output"))
      (node (ref "LED17") (pin "4") (pinfunction "DI_4") (pintype "input"))
    )
    (net (code "59") (name "Net-(LED17-DO)") (class "Default")
      (node (ref "LED17") (pin "2") (pinfunction "DO_2") (pintype "output"))
      (node (ref "LED18") (pin "4") (pinfunction "DI_4") (pintype "input"))
    )
    (net (code "60") (name "Net-(LED18-DO)") (class "Default")
      (node (ref "LED18") (pin "2") (pinfunction "DO_2") (pintype "output"))
      (node (ref "LED19") (pin "4") (pinfunction "DI_4") (pintype "input"))
    )
    (net (code "61") (name "Net-(LED19-DO)") (class "Default")
      (node (ref "LED19") (pin "2") (pinfunction "DO_2") (pintype "output"))
      (node (ref "LED20") (pin "4") (pinfunction "DI_4") (pintype "input"))
    )
    (net (code "62") (name "Net-(LED20-DO)") (class "Default")
      (node (ref "LED20") (pin "2") (pinfunction "DO_2") (pintype "output"))
      (node (ref "LED21") (pin "4") (pinfunction "DI_4") (pintype "input"))
    )
    (net (code "63") (name "Net-(LED21-DO)") (class "Default")
      (node (ref "LED21") (pin "2") (pinfunction "DO_2") (pintype "output"))
      (node (ref "LED22") (pin "4") (pinfunction "DI_4") (pintype "input"))
    )
    (net (code "64") (name "Net-(LED22-DO)") (class "Default")
      (node (ref "LED22") (pin "2") (pinfunction "DO_2") (pintype "output"))
      (node (ref "LED23") (pin "4") (pinfunction "DI_4") (pintype "input"))
    )
    (net (code "65") (name "Net-(LED23-DO)") (class "Default")
      (node (ref "LED23") (pin "2") (pinfunction "DO_2") (pintype "output"))
      (node (ref "LED24") (pin "4") (pinfunction "DI_4") (pintype "input"))
    )
    (net (code "66") (name "Net-(U$9-OUT1)") (class "Default")
      (node (ref "JP4") (pin "1") (pinfunction "1_1") (pintype "passive"))
      (node (ref "U$9") (pin "P$3") (pinfunction "OUT1_P$3") (pintype "bidirectional"))
    )
    (net (code "67") (name "Net-(U$9-OUT2)") (class "Default")
      (node (ref "JP4") (pin "2") (pinfunction "2_2") (pintype "passive"))
      (node (ref "U$9") (pin "P$8") (pinfunction "OUT2_P$8") (pintype "bidirectional"))
    )
    (net (code "68") (name "Net-(U$9-OUT3)") (class "Default")
      (node (ref "JP5") (pin "1") (pinfunction "1_1") (pintype "passive"))
      (node (ref "U$9") (pin "P$13") (pinfunction "OUT3_P$13") (pintype "bidirectional"))
    )
    (net (code "69") (name "Net-(U$9-OUT4)") (class "Default")
      (node (ref "JP5") (pin "2") (pinfunction "2_2") (pintype "passive"))
      (node (ref "U$9") (pin "P$18") (pinfunction "OUT4_P$18") (pintype "bidirectional"))
    )
    (net (code "70") (name "Net-(U$13-S)") (class "Default")
      (node (ref "U$13") (pin "2") (pinfunction "S_2") (pintype "passive"))
      (node (ref "X1") (pin "3") (pinfunction "VO_3") (pintype "input"))
    )
    (net (code "71") (name "Net-(U$15-SLEEP)") (class "Default")
      (node (ref "U$15") (pin "RST") (pinfunction "RST_RST") (pintype "input"))
      (node (ref "U$15") (pin "SLP") (pinfunction "SLEEP_SLP") (pintype "input"))
    )
    (net (code "72") (name "Net-(U$17-IN)") (class "Default")
      (node (ref "C5") (pin "2") (pinfunction "2_2") (pintype "bidirectional"))
      (node (ref "L3") (pin "P$2") (pinfunction "P$2_P$2") (pintype "bidirectional"))
      (node (ref "U$17") (pin "P$1") (pinfunction "IN_P$1") (pintype "bidirectional"))
    )
    (net (code "73") (name "Net-(U$60-XTAL1)") (class "Default")
      (node (ref "C15") (pin "1") (pinfunction "1_1") (pintype "bidirectional"))
      (node (ref "R10") (pin "1") (pinfunction "1_1") (pintype "bidirectional"))
      (node (ref "U$60") (pin "P$1") (pinfunction "XTAL1_P$1") (pintype "bidirectional"))
      (node (ref "U1") (pin "17") (pinfunction "XTAL1_17") (pintype "bidirectional"))
    )
    (net (code "74") (name "Net-(U$60-XTAL2)") (class "Default")
      (node (ref "C16") (pin "1") (pinfunction "1_1") (pintype "bidirectional"))
      (node (ref "R10") (pin "2") (pinfunction "2_2") (pintype "bidirectional"))
      (node (ref "U$60") (pin "P$3") (pinfunction "XTAL2_P$3") (pintype "bidirectional"))
      (node (ref "U1") (pin "16") (pinfunction "XTAL2_16") (pintype "bidirectional"))
    )
    (net (code "75") (name "Net-(U1-AREF)") (class "Default")
      (node (ref "C13") (pin "1") (pinfunction "1_1") (pintype "bidirectional"))
      (node (ref "U1") (pin "42") (pinfunction "AREF_42") (pintype "bidirectional"))
    )
    (net (code "76") (name "Net-(U1-D+)") (class "Default")
      (node (ref "R8") (pin "1") (pinfunction "1_1") (pintype "bidirectional"))
      (node (ref "U1") (pin "4") (pinfunction "D+_4") (pintype "bidirectional"))
    )
    (net (code "77") (name "Net-(U1-D-)") (class "Default")
      (node (ref "R7") (pin "1") (pinfunction "1_1") (pintype "bidirectional"))
      (node (ref "U1") (pin "3") (pinfunction "D-_3") (pintype "bidirectional"))
    )
    (net (code "78") (name "Net-(U1-UCAP)") (class "Default")
      (node (ref "C14") (pin "1") (pinfunction "1_1") (pintype "bidirectional"))
      (node (ref "U1") (pin "6") (pinfunction "UCAP_6") (pintype "bidirectional"))
    )
    (net (code "79") (name "unconnected-(LED24-DO-Pad2)") (class "Default")
      (node (ref "LED24") (pin "2") (pinfunction "DO_2") (pintype "output"))
    )
    (net (code "80") (name "unconnected-(U$15-PadEN)") (class "Default")
      (node (ref "U$15") (pin "EN") (pinfunction "EN_EN") (pintype "input"))
    )
    (net (code "81") (name "unconnected-(U$15-PadMS1)") (class "Default")
      (node (ref "U$15") (pin "MS1") (pinfunction "MS1_MS1") (pintype "input"))
    )
    (net (code "82") (name "unconnected-(U$15-PadMS2)") (class "Default")
      (node (ref "U$15") (pin "MS2") (pinfunction "MS2_MS2") (pintype "input"))
    )
    (net (code "83") (name "unconnected-(U$15-PadMS3)") (class "Default")
      (node (ref "U$15") (pin "MS3") (pinfunction "MS3_MS3") (pintype "input"))
    )
    (net (code "84") (name "unconnected-(U$16-PadEN)") (class "Default")
      (node (ref "U$16") (pin "EN") (pinfunction "EN_EN") (pintype "input"))
    )
    (net (code "85") (name "unconnected-(U$16-PadMS1)") (class "Default")
      (node (ref "U$16") (pin "MS1") (pinfunction "MS1_MS1") (pintype "input"))
    )
    (net (code "86") (name "unconnected-(U$16-PadMS2)") (class "Default")
      (node (ref "U$16") (pin "MS2") (pinfunction "MS2_MS2") (pintype "input"))
    )
    (net (code "87") (name "unconnected-(U$16-PadMS3)") (class "Default")
      (node (ref "U$16") (pin "MS3") (pinfunction "MS3_MS3") (pintype "input"))
    )
    (net (code "88") (name "unconnected-(U$16-PadRST)") (class "Default")
      (node (ref "U$16") (pin "RST") (pinfunction "RST_RST") (pintype "input"))
    )
    (net (code "89") (name "unconnected-(U$16-SLEEP-PadSLP)") (class "Default")
      (node (ref "U$16") (pin "SLP") (pinfunction "SLEEP_SLP") (pintype "input"))
    )
    (net (code "90") (name "unconnected-(X1-DB0-Pad7)") (class "Default")
      (node (ref "X1") (pin "7") (pinfunction "DB0_7") (pintype "bidirectional"))
    )
    (net (code "91") (name "unconnected-(X1-DB1-Pad8)") (class "Default")
      (node (ref "X1") (pin "8") (pinfunction "DB1_8") (pintype "bidirectional"))
    )
    (net (code "92") (name "unconnected-(X1-DB2-Pad9)") (class "Default")
      (node (ref "X1") (pin "9") (pinfunction "DB2_9") (pintype "bidirectional"))
    )
    (net (code "93") (name "unconnected-(X1-DB3-Pad10)") (class "Default")
      (node (ref "X1") (pin "10") (pinfunction "DB3_10") (pintype "bidirectional"))
    )
  )
)
